# SFE_SC.net
KiCad netlist of a schematic drawn in Altium Designer
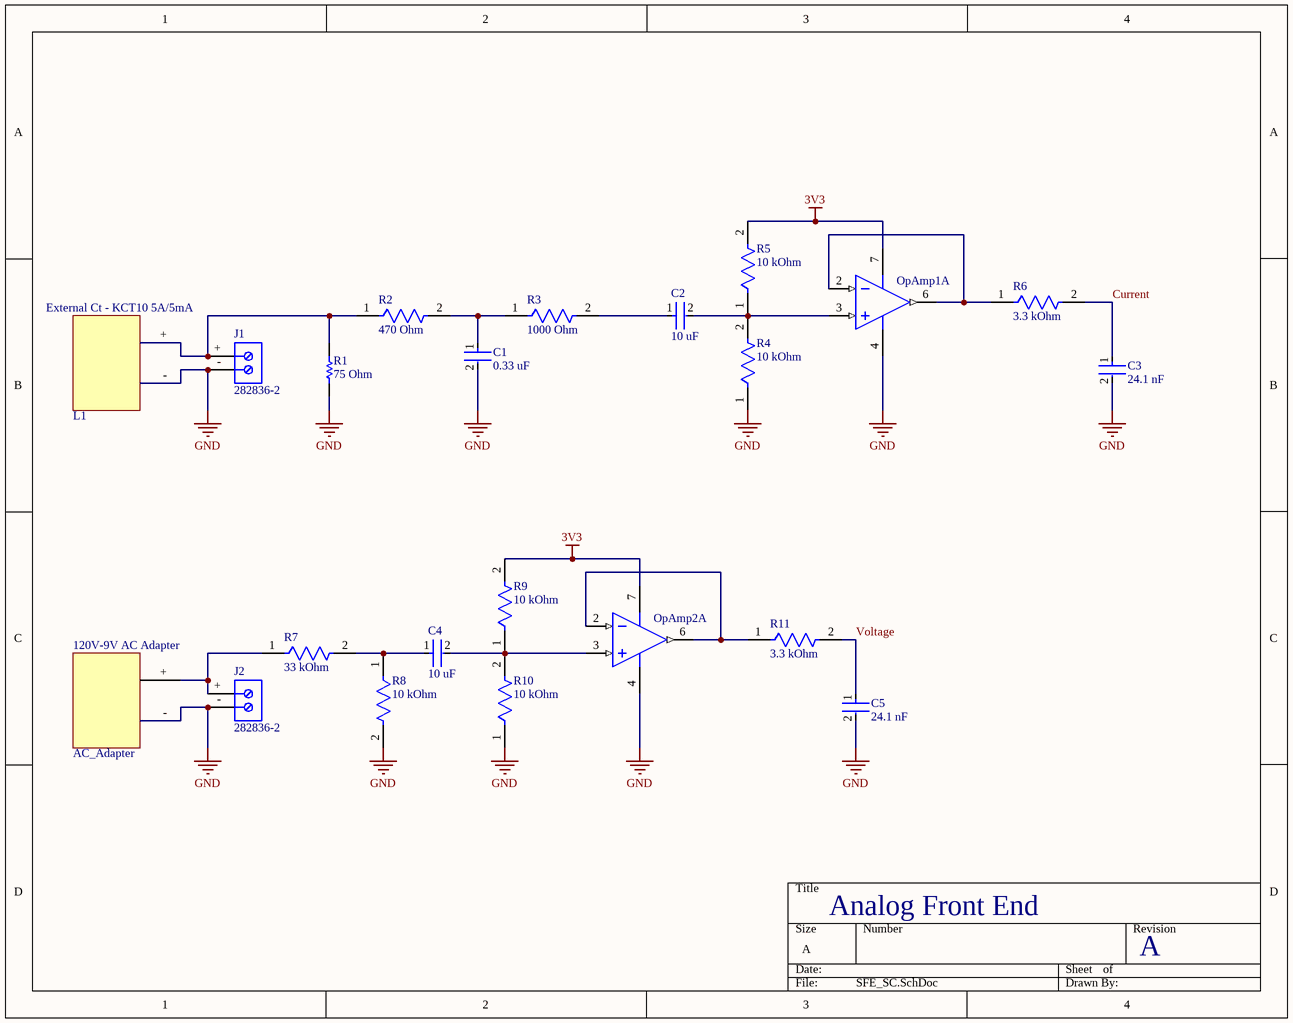
[diagram p0: SFE_SC.SchDoc]

(export (version "E")
  (design (tool "Eeschema 10.0.6"))
  (components
    (comp (ref "Adapter") (value "AC_Adapter") (libsource (lib "Schlib2") (part "AC_Adapter")))
    (comp (ref "C1")
      (value "0.33 uF")
      (footprint "FP-CGA3E-0_3-0_1-IPC_B")
      (description "Cap Ceramic 330nF 50V X7R 10% Pad SMD 0603 +125°C Automotive T/R")
      (fields (field (name "TOLERANCE") "10%"))
      (libsource (lib "Altium Content Vault") (part "b4654b650e69147ec39a6b967a45e02"))
    )
    (comp (ref "C2")
      (value "10 uF")
      (footprint "FP-CL21-IPC_B")
      (description "CL21 Series 0805 10uF 10V ±10% Tolerance X5R Multilayer Ceramic Chip Capacitor")
      (fields (field (name "VOLTAGE") "10V") (field (name "TOLERANCE") "10%"))
      (libsource (lib "Altium Content Vault") (part "b4654b650e69147ec39a6b967a45e02"))
    )
    (comp (ref "C3")
      (value "24.1 nF")
      (footprint "FP-CL10-IPC_C")
      (description "Cap Ceramic 22nF 50V X7R ±10% Pad SMD 0603 +125°C T/R")
      (fields (field (name "VOLTAGE") "50V") (field (name "TOLERANCE") "10%"))
      (libsource (lib "Altium Content Vault") (part "b4654b650e69147ec39a6b967a45e02"))
    )
    (comp (ref "C4")
      (value "10 uF")
      (footprint "FP-CL21-IPC_B")
      (description "CL21 Series 0805 10uF 10V ±10% Tolerance X5R Multilayer Ceramic Chip Capacitor")
      (fields (field (name "VOLTAGE") "10V") (field (name "TOLERANCE") "10%"))
      (libsource (lib "Altium Content Vault") (part "b4654b650e69147ec39a6b967a45e02"))
    )
    (comp (ref "C5")
      (value "24.1 nF")
      (footprint "FP-CL10-IPC_C")
      (description "Cap Ceramic 22nF 50V X7R ±10% Pad SMD 0603 +125°C T/R")
      (fields (field (name "VOLTAGE") "50V") (field (name "TOLERANCE") "10%"))
      (libsource (lib "Altium Content Vault") (part "b4654b650e69147ec39a6b967a45e02"))
    )
    (comp (ref "Ct clamp") (value "L1") (libsource (lib "Schlib2") (part "Component_1")))
    (comp (ref "J1")
      (value "282836-2")
      (footprint "TECO-282836-2_V")
      (description "Female Header, Pitch 5 mm, 1 x 2 Position, Height 10 mm, Tail Length 3.5 mm, Rohs, Bulk")
      (fields (field (name "VOLTAGE") "300V") (field (name "MANUFACTURER") "TE Connectivity"))
      (libsource (lib "Altium Content Vault") (part "CN-1P-F-TB2"))
    )
    (comp (ref "J2")
      (value "282836-2")
      (footprint "TECO-282836-2_V")
      (description "Female Header, Pitch 5 mm, 1 x 2 Position, Height 10 mm, Tail Length 3.5 mm, Rohs, Bulk")
      (fields (field (name "VOLTAGE") "300V") (field (name "MANUFACTURER") "TE Connectivity"))
      (libsource (lib "Altium Content Vault") (part "CN-1P-F-TB2"))
    )
    (comp (ref "OpAmp1")
      (value "TLV2461ID")
      (footprint "D0008A_N")
      (fields (field (name "MANUFACTURER") "Texas Instruments"))
      (libsource (lib "Altium Content Vault") (part "TI-TLV24X1-8"))
    )
    (comp (ref "OpAmp2")
      (value "TLV2461ID")
      (footprint "D0008A_N")
      (fields (field (name "MANUFACTURER") "Texas Instruments"))
      (libsource (lib "Altium Content Vault") (part "TI-TLV24X1-8"))
    )
    (comp (ref "R1")
      (value "75 Ohm")
      (footprint "RESC3225X60X45LL20T20")
      (fields (field (name "PART NUMBER") "CRCW121075R0FKEAHP") (field (name "MANUFACTURER") "Vishay Dale"))
      (libsource (lib "Altium Content Vault") (part "RES"))
    )
    (comp (ref "R2")
      (value "470 Ohm")
      (footprint "FP-CRGCQ0603-IPC_C")
      (description "CRGCQ 0603 470R 1%")
      (fields
        (field (name "OCTOPART") "https://octopart.com/crgcq0603f470r-te+connectivity-91018076")
        (field (name "MANUFACTURER") "TE Connectivity")
      )
      (libsource (lib "Altium Content Vault") (part "1029c3af85768c4190bb7ad29bc67b5"))
    )
    (comp (ref "R3")
      (value "1000 Ohm")
      (footprint "FP-RMCF0603-MFG")
      (description "1kΩ ±1% 0.1W 0603 Thick Film Chip Resistor AEC-Q200 compliant")
      (fields (field (name "TOLERANCE") "1%"))
      (libsource (lib "Altium Content Vault") (part "1029c3af85768c4190bb7ad29bc67b5"))
    )
    (comp (ref "R4")
      (value "10 kOhm")
      (footprint "FP-RC0603-0_55-IPC_C")
      (description "RES 10K OHM 1% 1/10W 0603")
      (fields (field (name "TOLERANCE") "1%"))
      (libsource (lib "Altium Content Vault") (part "1029c3af85768c4190bb7ad29bc67b5"))
    )
    (comp (ref "R5")
      (value "10 kOhm")
      (footprint "FP-RC0603-0_55-IPC_C")
      (description "RES 10K OHM 1% 1/10W 0603")
      (fields (field (name "TOLERANCE") "1%"))
      (libsource (lib "Altium Content Vault") (part "1029c3af85768c4190bb7ad29bc67b5"))
    )
    (comp (ref "R6")
      (value "3.3 kOhm")
      (footprint "FP-RC0603-0_55-MFG")
      (fields (field (name "TOLERANCE") "1%"))
      (libsource (lib "Altium Content Vault") (part "1029c3af85768c4190bb7ad29bc67b5"))
    )
    (comp (ref "R7")
      (value "33 kOhm")
      (footprint "FP-RT0402-MFG")
      (description "RES SMD 33K OHM 0.1% 1/16W 0402")
      (fields
        (field (name "MANUFACTURER PART NUMBER") "RT0402BRD0733KL")
        (field (name "OCTOPART") "https://octopart.com/rt0402brd0733kl-yageo-1394589")
      )
      (libsource (lib "Altium Content Vault") (part "1029c3af85768c4190bb7ad29bc67b5"))
    )
    (comp (ref "R8")
      (value "10 kOhm")
      (footprint "FP-RMCF0603-MFG")
      (description "10kΩ ±1% 0.1W 0603 Thick Film Chip Resistor AEC-Q200 compliant")
      (fields (field (name "TOLERANCE") "1%"))
      (libsource (lib "Altium Content Vault") (part "1029c3af85768c4190bb7ad29bc67b5"))
    )
    (comp (ref "R9")
      (value "10 kOhm")
      (footprint "FP-RC0603-0_55-IPC_C")
      (description "RES 10K OHM 1% 1/10W 0603")
      (fields (field (name "TOLERANCE") "1%"))
      (libsource (lib "Altium Content Vault") (part "1029c3af85768c4190bb7ad29bc67b5"))
    )
    (comp (ref "R10")
      (value "10 kOhm")
      (footprint "FP-RC0603-0_55-IPC_C")
      (description "RES 10K OHM 1% 1/10W 0603")
      (fields (field (name "TOLERANCE") "1%"))
      (libsource (lib "Altium Content Vault") (part "1029c3af85768c4190bb7ad29bc67b5"))
    )
    (comp (ref "R11")
      (value "3.3 kOhm")
      (footprint "FP-RC0603-0_55-MFG")
      (fields (field (name "TOLERANCE") "1%"))
      (libsource (lib "Altium Content Vault") (part "1029c3af85768c4190bb7ad29bc67b5"))
    )
  )
  (nets
    (net (code "1") (name "/Current") (class "Default")
      (node (ref "C3") (pin "1") (pinfunction "1_1") (pintype "passive"))
      (node (ref "R6") (pin "2") (pinfunction "2_2") (pintype "passive"))
    )
    (net (code "2") (name "/Voltage") (class "Default")
      (node (ref "C5") (pin "1") (pinfunction "1_1") (pintype "passive"))
      (node (ref "R11") (pin "2") (pinfunction "2_2") (pintype "passive"))
    )
    (net (code "3") (name "3V3") (class "Default")
      (node (ref "OpAmp1") (pin "7") (pinfunction "VDD+_7") (pintype "power_in"))
      (node (ref "OpAmp2") (pin "7") (pinfunction "VDD+_7") (pintype "power_in"))
      (node (ref "R5") (pin "2") (pinfunction "2_2") (pintype "passive"))
      (node (ref "R9") (pin "2") (pinfunction "2_2") (pintype "passive"))
    )
    (net (code "4") (name "GND") (class "Default")
      (node (ref "Adapter") (pin "-") (pinfunction "-_-") (pintype "passive"))
      (node (ref "C1") (pin "2") (pinfunction "2_2") (pintype "passive"))
      (node (ref "C3") (pin "2") (pinfunction "2_2") (pintype "passive"))
      (node (ref "C5") (pin "2") (pinfunction "2_2") (pintype "passive"))
      (node (ref "Ct clamp") (pin "-") (pinfunction "-_-") (pintype "passive"))
      (node (ref "J1") (pin "-") (pinfunction "2_-") (pintype "passive"))
      (node (ref "J2") (pin "-") (pinfunction "2_-") (pintype "passive"))
      (node (ref "OpAmp1") (pin "4") (pinfunction "GND_4") (pintype "power_in"))
      (node (ref "OpAmp2") (pin "4") (pinfunction "GND_4") (pintype "power_in"))
      (node (ref "R1") (pin "1") (pinfunction "1_1") (pintype "passive"))
      (node (ref "R10") (pin "1") (pinfunction "1_1") (pintype "passive"))
      (node (ref "R4") (pin "1") (pinfunction "1_1") (pintype "passive"))
      (node (ref "R8") (pin "2") (pinfunction "2_2") (pintype "passive"))
    )
    (net (code "5") (name "Net-(C1-Pad1)") (class "Default")
      (node (ref "C1") (pin "1") (pinfunction "1_1") (pintype "passive"))
      (node (ref "R2") (pin "2") (pinfunction "2_2") (pintype "passive"))
      (node (ref "R3") (pin "1") (pinfunction "1_1") (pintype "passive"))
    )
    (net (code "6") (name "Net-(C2-Pad1)") (class "Default")
      (node (ref "C2") (pin "1") (pinfunction "1_1") (pintype "passive"))
      (node (ref "R3") (pin "2") (pinfunction "2_2") (pintype "passive"))
    )
    (net (code "7") (name "Net-(C4-Pad1)") (class "Default")
      (node (ref "C4") (pin "1") (pinfunction "1_1") (pintype "passive"))
      (node (ref "R7") (pin "2") (pinfunction "2_2") (pintype "passive"))
      (node (ref "R8") (pin "1") (pinfunction "1_1") (pintype "passive"))
    )
    (net (code "8") (name "Net-(J1-1)") (class "Default")
      (node (ref "Ct clamp") (pin "+") (pinfunction "+_+") (pintype "passive"))
      (node (ref "J1") (pin "+") (pinfunction "1_+") (pintype "passive"))
      (node (ref "R1") (pin "2") (pinfunction "2_2") (pintype "passive"))
      (node (ref "R2") (pin "1") (pinfunction "1_1") (pintype "passive"))
    )
    (net (code "9") (name "Net-(J2-1)") (class "Default")
      (node (ref "J2") (pin "+") (pinfunction "1_+") (pintype "passive"))
      (node (ref "R7") (pin "1") (pinfunction "1_1") (pintype "passive"))
    )
    (net (code "10") (name "Net-(OpAmp1A-IN+)") (class "Default")
      (node (ref "C2") (pin "2") (pinfunction "2_2") (pintype "passive"))
      (node (ref "OpAmp1") (pin "3") (pinfunction "IN+_3") (pintype "input"))
      (node (ref "R4") (pin "2") (pinfunction "2_2") (pintype "passive"))
      (node (ref "R5") (pin "1") (pinfunction "1_1") (pintype "passive"))
    )
    (net (code "11") (name "Net-(OpAmp1A-IN-)") (class "Default")
      (node (ref "OpAmp1") (pin "2") (pinfunction "IN-_2") (pintype "input"))
      (node (ref "OpAmp1") (pin "6") (pinfunction "OUT_6") (pintype "output"))
      (node (ref "R6") (pin "1") (pinfunction "1_1") (pintype "passive"))
    )
    (net (code "12") (name "Net-(OpAmp2A-IN+)") (class "Default")
      (node (ref "C4") (pin "2") (pinfunction "2_2") (pintype "passive"))
      (node (ref "OpAmp2") (pin "3") (pinfunction "IN+_3") (pintype "input"))
      (node (ref "R10") (pin "2") (pinfunction "2_2") (pintype "passive"))
      (node (ref "R9") (pin "1") (pinfunction "1_1") (pintype "passive"))
    )
    (net (code "13") (name "Net-(OpAmp2A-IN-)") (class "Default")
      (node (ref "OpAmp2") (pin "2") (pinfunction "IN-_2") (pintype "input"))
      (node (ref "OpAmp2") (pin "6") (pinfunction "OUT_6") (pintype "output"))
      (node (ref "R11") (pin "1") (pinfunction "1_1") (pintype "passive"))
    )
    (net (code "14") (name "unconnected-(Adapter-Pad+)") (class "Default")
      (node (ref "Adapter") (pin "+") (pinfunction "+_+") (pintype "passive"))
    )
  )
)
